# rectifier_circuit.net
KiCad netlist of a schematic drawn in EAGLE
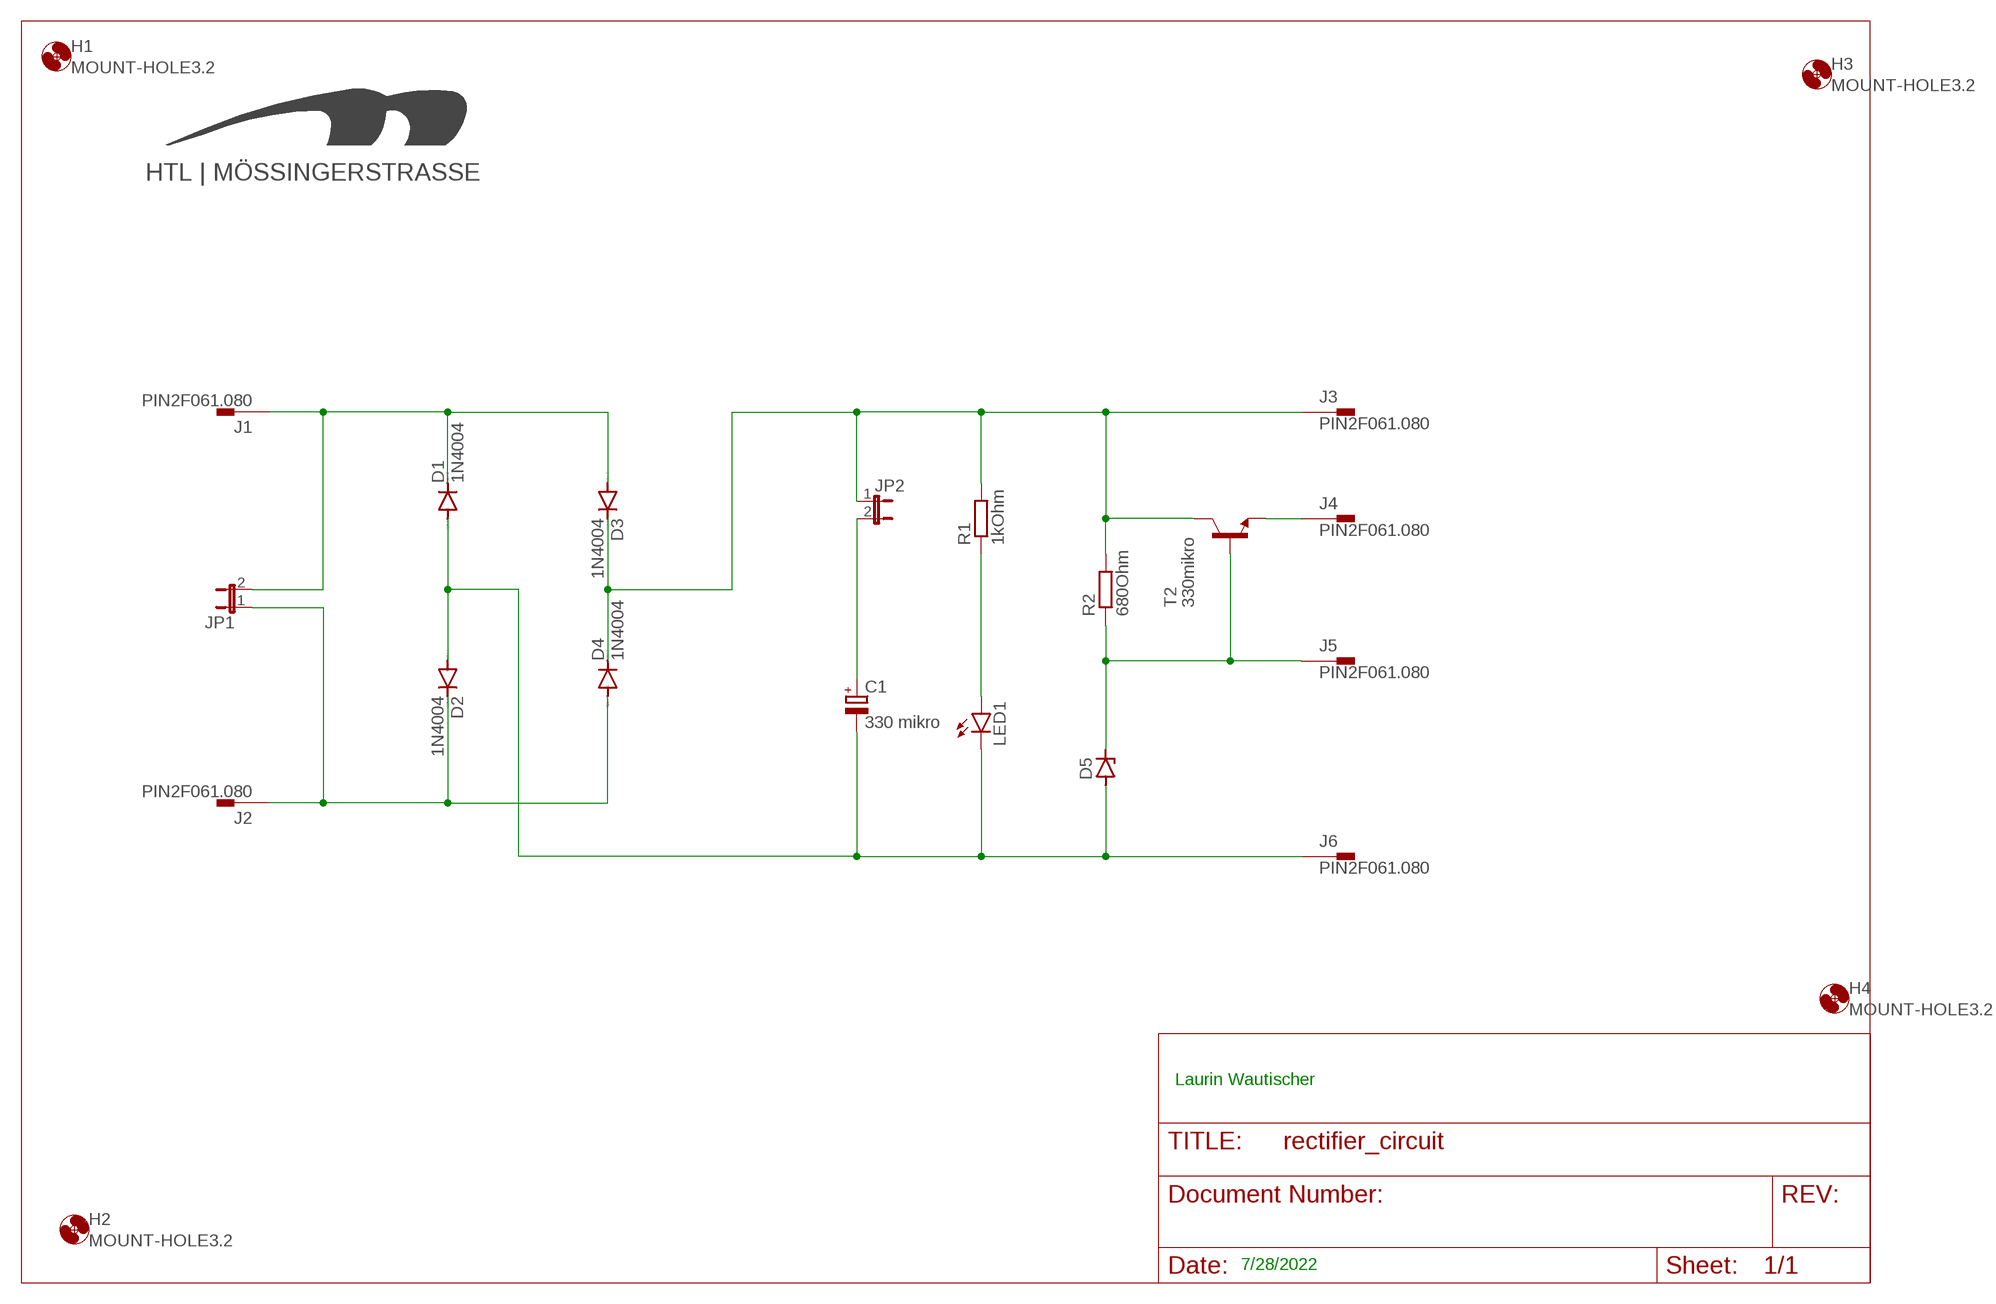
[diagram p0: schematic, sheet 1]

(export (version "E")
  (design (tool "Eeschema 10.0.6"))
  (components
    (comp (ref "C1")
      (value "330 mikro")
      (footprint "eagle-import:E5-13")
      (libsource (lib "eagle-import") (part "CPOL-EUE5-13"))
    )
    (comp (ref "D1")
      (value "1N4004")
      (footprint "eagle-import:DO41-10")
      (libsource (lib "eagle-import") (part "1N4004"))
    )
    (comp (ref "D2")
      (value "1N4004")
      (footprint "eagle-import:DO41-10")
      (libsource (lib "eagle-import") (part "1N4004"))
    )
    (comp (ref "D3")
      (value "1N4004")
      (footprint "eagle-import:DO41-10")
      (libsource (lib "eagle-import") (part "1N4004"))
    )
    (comp (ref "D4")
      (value "1N4004")
      (footprint "eagle-import:DO41-10")
      (libsource (lib "eagle-import") (part "1N4004"))
    )
    (comp (ref "D5")
      (value "ZENER-DIODEDO35Z10")
      (footprint "eagle-import:DO35Z10")
      (libsource (lib "eagle-import") (part "ZENER-DIODEDO35Z10"))
    )
    (comp (ref "H1")
      (value "MOUNT-HOLE3.2")
      (footprint "eagle-import:3,2")
      (libsource (lib "eagle-import") (part "MOUNT-HOLE3.2"))
    )
    (comp (ref "H2")
      (value "MOUNT-HOLE3.2")
      (footprint "eagle-import:3,2")
      (libsource (lib "eagle-import") (part "MOUNT-HOLE3.2"))
    )
    (comp (ref "H3")
      (value "MOUNT-HOLE3.2")
      (footprint "eagle-import:3,2")
      (libsource (lib "eagle-import") (part "MOUNT-HOLE3.2"))
    )
    (comp (ref "H4")
      (value "MOUNT-HOLE3.2")
      (footprint "eagle-import:3,2")
      (libsource (lib "eagle-import") (part "MOUNT-HOLE3.2"))
    )
    (comp (ref "J1")
      (value "PIN2F061.080")
      (footprint "eagle-import:F061.080")
      (libsource (lib "eagle-import") (part "PIN2F061.080"))
    )
    (comp (ref "J2")
      (value "PIN2F061.080")
      (footprint "eagle-import:F061.080")
      (libsource (lib "eagle-import") (part "PIN2F061.080"))
    )
    (comp (ref "J3")
      (value "PIN2F061.080")
      (footprint "eagle-import:F061.080")
      (libsource (lib "eagle-import") (part "PIN2F061.080"))
    )
    (comp (ref "J4")
      (value "PIN2F061.080")
      (footprint "eagle-import:F061.080")
      (libsource (lib "eagle-import") (part "PIN2F061.080"))
    )
    (comp (ref "J5")
      (value "PIN2F061.080")
      (footprint "eagle-import:F061.080")
      (libsource (lib "eagle-import") (part "PIN2F061.080"))
    )
    (comp (ref "J6")
      (value "PIN2F061.080")
      (footprint "eagle-import:F061.080")
      (libsource (lib "eagle-import") (part "PIN2F061.080"))
    )
    (comp (ref "JP1")
      (value "JP1E")
      (footprint "eagle-import:JP1")
      (libsource (lib "eagle-import") (part "JP1E"))
    )
    (comp (ref "JP2")
      (value "JP1E")
      (footprint "eagle-import:JP1")
      (libsource (lib "eagle-import") (part "JP1E"))
    )
    (comp (ref "LED1")
      (value "LED5MM")
      (footprint "eagle-import:LED5MM")
      (libsource (lib "eagle-import") (part "LED5MM"))
    )
    (comp (ref "R1")
      (value "1kOhm")
      (footprint "eagle-import:0207_10")
      (libsource (lib "eagle-import") (part "R-EU_0207/10"))
    )
    (comp (ref "R2")
      (value "680Ohm")
      (footprint "eagle-import:0207_10")
      (libsource (lib "eagle-import") (part "R-EU_0207/10"))
    )
    (comp (ref "T2")
      (value "330mikro")
      (footprint "eagle-import:TO92-CBE")
      (libsource (lib "eagle-import") (part "-NPN-TO92-CBE2N4124"))
    )
    (comp (ref "U$1")
      (value "HTL_LOGOBOT_15MM")
      (footprint "eagle-import:LOGOBOT_15")
      (libsource (lib "eagle-import") (part "HTL_LOGOBOT_15MM"))
    )
  )
  (nets
    (net (code "1") (name "Net-(C1-Pad+)") (class "Default")
      (node (ref "C1") (pin "+") (pinfunction "+_+") (pintype "passive"))
      (node (ref "JP2") (pin "2") (pinfunction "2_2") (pintype "passive"))
    )
    (net (code "2") (name "Net-(D1-PadC)") (class "Default")
      (node (ref "D1") (pin "C") (pinfunction "C_C") (pintype "passive"))
      (node (ref "D3") (pin "A") (pinfunction "A_A") (pintype "passive"))
      (node (ref "J1") (pin "1A") (pinfunction "1_1A") (pintype "passive"))
      (node (ref "J1") (pin "1B") (pinfunction "1_1B") (pintype "passive"))
      (node (ref "JP1") (pin "2") (pinfunction "2_2") (pintype "passive"))
    )
    (net (code "3") (name "Net-(D2-PadC)") (class "Default")
      (node (ref "D2") (pin "C") (pinfunction "C_C") (pintype "passive"))
      (node (ref "D4") (pin "A") (pinfunction "A_A") (pintype "passive"))
      (node (ref "J2") (pin "1A") (pinfunction "1_1A") (pintype "passive"))
      (node (ref "J2") (pin "1B") (pinfunction "1_1B") (pintype "passive"))
      (node (ref "JP1") (pin "1") (pinfunction "1_1") (pintype "passive"))
    )
    (net (code "4") (name "Net-(D3-PadC)") (class "Default")
      (node (ref "D3") (pin "C") (pinfunction "C_C") (pintype "passive"))
      (node (ref "D4") (pin "C") (pinfunction "C_C") (pintype "passive"))
      (node (ref "J3") (pin "1A") (pinfunction "1_1A") (pintype "passive"))
      (node (ref "J3") (pin "1B") (pinfunction "1_1B") (pintype "passive"))
      (node (ref "JP2") (pin "1") (pinfunction "1_1") (pintype "passive"))
      (node (ref "R1") (pin "2") (pinfunction "2_2") (pintype "passive"))
      (node (ref "R2") (pin "2") (pinfunction "2_2") (pintype "passive"))
      (node (ref "T2") (pin "C") (pinfunction "C_C") (pintype "passive"))
    )
    (net (code "5") (name "Net-(D5-PadC)") (class "Default")
      (node (ref "D5") (pin "C") (pinfunction "C_C") (pintype "passive"))
      (node (ref "J5") (pin "1A") (pinfunction "1_1A") (pintype "passive"))
      (node (ref "J5") (pin "1B") (pinfunction "1_1B") (pintype "passive"))
      (node (ref "R2") (pin "1") (pinfunction "1_1") (pintype "passive"))
      (node (ref "T2") (pin "B") (pinfunction "B_B") (pintype "passive"))
    )
    (net (code "6") (name "Net-(J4-1-Pad1A)") (class "Default")
      (node (ref "J4") (pin "1A") (pinfunction "1_1A") (pintype "passive"))
      (node (ref "J4") (pin "1B") (pinfunction "1_1B") (pintype "passive"))
      (node (ref "T2") (pin "E") (pinfunction "E_E") (pintype "passive"))
    )
    (net (code "7") (name "Net-(LED1-C)") (class "Default")
      (node (ref "C1") (pin "-") (pinfunction "-_-") (pintype "passive"))
      (node (ref "D1") (pin "A") (pinfunction "A_A") (pintype "passive"))
      (node (ref "D2") (pin "A") (pinfunction "A_A") (pintype "passive"))
      (node (ref "D5") (pin "A") (pinfunction "A_A") (pintype "passive"))
      (node (ref "J6") (pin "1A") (pinfunction "1_1A") (pintype "passive"))
      (node (ref "J6") (pin "1B") (pinfunction "1_1B") (pintype "passive"))
      (node (ref "LED1") (pin "K") (pinfunction "C_K") (pintype "passive"))
    )
    (net (code "8") (name "Net-(LED1-PadA)") (class "Default")
      (node (ref "LED1") (pin "A") (pinfunction "A_A") (pintype "passive"))
      (node (ref "R1") (pin "1") (pinfunction "1_1") (pintype "passive"))
    )
  )
)
